# 4_GNSS.net
KiCad netlist of a schematic drawn in Altium Designer
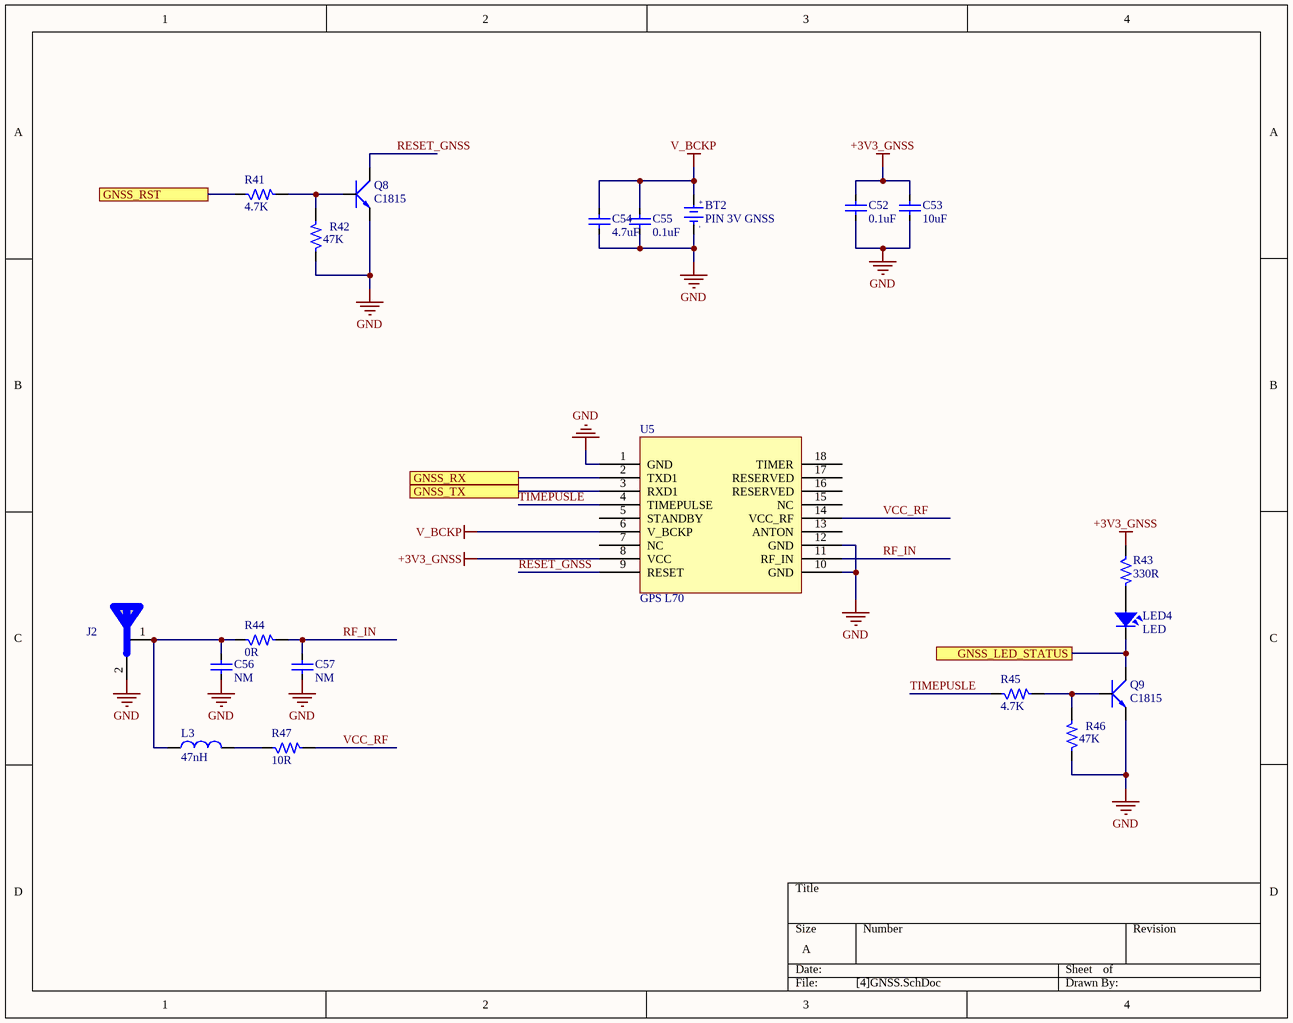
[diagram p0: [4]GNSS.SchDoc]

(export (version "E")
  (design (tool "Eeschema 10.0.6"))
  (components
    (comp (ref "BT2")
      (value "PIN 3V GNSS")
      (footprint "CR1220 SMD")
      (description "Battery 3VDC")
      (libsource (lib "GPS_Traking_V1_1") (part "PIN 3V"))
    )
    (comp (ref "C52")
      (value "0.1uF")
      (footprint "CAP_0805")
      (description "Capacitor")
      (fields (field (name "PUBLISHER") "Altium Limited"))
      (libsource (lib "My Library") (part "CapSMD"))
    )
    (comp (ref "C53")
      (value "10uF")
      (footprint "CAP_0805")
      (description "Capacitor")
      (fields (field (name "PUBLISHER") "Altium Limited"))
      (libsource (lib "My Library") (part "CapSMD"))
    )
    (comp (ref "C54")
      (value "4.7uF")
      (footprint "CAP_0805")
      (description "Capacitor")
      (fields (field (name "PUBLISHER") "Altium Limited"))
      (libsource (lib "My Library") (part "CapSMD"))
    )
    (comp (ref "C55")
      (value "0.1uF")
      (footprint "CAP_0805")
      (description "Capacitor")
      (fields (field (name "PUBLISHER") "Altium Limited"))
      (libsource (lib "My Library") (part "CapSMD"))
    )
    (comp (ref "C56")
      (value "NM")
      (footprint "CAP_0805")
      (description "Capacitor")
      (fields (field (name "PUBLISHER") "Altium Limited"))
      (libsource (lib "My Library") (part "CapSMD"))
    )
    (comp (ref "C57")
      (value "NM")
      (footprint "CAP_0805")
      (description "Capacitor")
      (fields (field (name "PUBLISHER") "Altium Limited"))
      (libsource (lib "My Library") (part "CapSMD"))
    )
    (comp (ref "J2")
      (value "GPS_ANTENNA")
      (footprint "Antenna-MCX5.08-H5")
      (libsource (lib "GPS_Traking_V1_1") (part "ANTEN"))
    )
    (comp (ref "L3")
      (value "47nH")
      (footprint "RES-SMD-0805")
      (description "Inductor")
      (libsource (lib "GPS_Traking_V1_1") (part "L1"))
    )
    (comp (ref "LED4")
      (value "LED")
      (footprint "LED-0805-Red")
      (description "LED Single colour Green and Red")
      (libsource (lib "My Library") (part "LED"))
    )
    (comp (ref "Q8")
      (value "C1815")
      (footprint "SOT23B")
      (description "NPN 600mW, ECB")
      (libsource (lib "GPS_Traking_V1_1") (part "C1815"))
    )
    (comp (ref "Q9")
      (value "C1815")
      (footprint "SOT23B")
      (description "NPN 600mW, ECB")
      (libsource (lib "GPS_Traking_V1_1") (part "C1815"))
    )
    (comp (ref "R41")
      (value "4.7K")
      (footprint "R0805")
      (description "Resistor SMD")
      (libsource (lib "GPS_Traking_V1_1") (part "RM"))
    )
    (comp (ref "R42")
      (value "47K")
      (footprint "R0805")
      (description "Resistor SMD")
      (libsource (lib "GPS_Traking_V1_1") (part "RM"))
    )
    (comp (ref "R43")
      (value "330R")
      (footprint "R0805")
      (description "Resistor SMD")
      (libsource (lib "GPS_Traking_V1_1") (part "RM"))
    )
    (comp (ref "R44")
      (value "0R")
      (footprint "R0805")
      (description "Resistor SMD")
      (libsource (lib "GPS_Traking_V1_1") (part "RM"))
    )
    (comp (ref "R45")
      (value "4.7K")
      (footprint "R0805")
      (description "Resistor SMD")
      (libsource (lib "GPS_Traking_V1_1") (part "RM"))
    )
    (comp (ref "R46")
      (value "47K")
      (footprint "R0805")
      (description "Resistor SMD")
      (libsource (lib "GPS_Traking_V1_1") (part "RM"))
    )
    (comp (ref "R47")
      (value "10R")
      (footprint "R0805")
      (description "Resistor SMD")
      (libsource (lib "GPS_Traking_V1_1") (part "RM"))
    )
    (comp (ref "U5")
      (value "GPS L70")
      (footprint "GPS L70")
      (libsource (lib "GPS_Traking_V1_1") (part "GPS L70"))
    )
  )
  (nets
    (net (code "1") (name "+3V3_GNSS") (class "Default")
      (node (ref "C52") (pin "2") (pinfunction "2_2") (pintype "passive"))
      (node (ref "C53") (pin "2") (pinfunction "2_2") (pintype "passive"))
      (node (ref "R43") (pin "1") (pinfunction "1_1") (pintype "passive"))
      (node (ref "U5") (pin "8") (pinfunction "VCC_8") (pintype "passive"))
    )
    (net (code "2") (name "/GNSS_LED_STATUS") (class "Default")
      (node (ref "LED4") (pin "2") (pinfunction "2_2") (pintype "passive"))
      (node (ref "Q9") (pin "2") (pinfunction "C_2") (pintype "passive"))
    )
    (net (code "3") (name "/GNSS_RST") (class "Default")
      (node (ref "R41") (pin "1") (pinfunction "1_1") (pintype "passive"))
    )
    (net (code "4") (name "/GNSS_RX") (class "Default")
      (node (ref "U5") (pin "2") (pinfunction "TXD1_2") (pintype "passive"))
    )
    (net (code "5") (name "/GNSS_TX") (class "Default")
      (node (ref "U5") (pin "3") (pinfunction "RXD1_3") (pintype "passive"))
    )
    (net (code "6") (name "/RESET_GNSS") (class "Default")
      (node (ref "Q8") (pin "2") (pinfunction "C_2") (pintype "passive"))
      (node (ref "U5") (pin "9") (pinfunction "RESET_9") (pintype "passive"))
    )
    (net (code "7") (name "/RF_IN") (class "Default")
      (node (ref "C57") (pin "2") (pinfunction "2_2") (pintype "passive"))
      (node (ref "R44") (pin "2") (pinfunction "2_2") (pintype "passive"))
      (node (ref "U5") (pin "11") (pinfunction "RF_IN_11") (pintype "passive"))
    )
    (net (code "8") (name "/TIMEPUSLE") (class "Default")
      (node (ref "R45") (pin "1") (pinfunction "1_1") (pintype "passive"))
      (node (ref "U5") (pin "4") (pinfunction "TIMEPULSE_4") (pintype "passive"))
    )
    (net (code "9") (name "/VCC_RF") (class "Default")
      (node (ref "R47") (pin "2") (pinfunction "2_2") (pintype "passive"))
      (node (ref "U5") (pin "14") (pinfunction "VCC_RF_14") (pintype "passive"))
    )
    (net (code "10") (name "GND") (class "Default")
      (node (ref "BT2") (pin "2") (pinfunction "GND_2") (pintype "passive"))
      (node (ref "C52") (pin "1") (pinfunction "1_1") (pintype "passive"))
      (node (ref "C53") (pin "1") (pinfunction "1_1") (pintype "passive"))
      (node (ref "C54") (pin "1") (pinfunction "1_1") (pintype "passive"))
      (node (ref "C55") (pin "1") (pinfunction "1_1") (pintype "passive"))
      (node (ref "C56") (pin "1") (pinfunction "1_1") (pintype "passive"))
      (node (ref "C57") (pin "1") (pinfunction "1_1") (pintype "passive"))
      (node (ref "J2") (pin "2") (pinfunction "GND_2") (pintype "passive"))
      (node (ref "Q8") (pin "1") (pinfunction "E_1") (pintype "passive"))
      (node (ref "Q9") (pin "1") (pinfunction "E_1") (pintype "passive"))
      (node (ref "R42") (pin "1") (pinfunction "1_1") (pintype "passive"))
      (node (ref "R46") (pin "1") (pinfunction "1_1") (pintype "passive"))
      (node (ref "U5") (pin "1") (pinfunction "GND_1") (pintype "passive"))
      (node (ref "U5") (pin "10") (pinfunction "GND_10") (pintype "passive"))
      (node (ref "U5") (pin "12") (pinfunction "GND_12") (pintype "passive"))
    )
    (net (code "11") (name "Net-(C56-Pad2)") (class "Default")
      (node (ref "C56") (pin "2") (pinfunction "2_2") (pintype "passive"))
      (node (ref "J2") (pin "1") (pinfunction "GND_1") (pintype "passive"))
      (node (ref "L3") (pin "1") (pinfunction "1_1") (pintype "passive"))
      (node (ref "R44") (pin "1") (pinfunction "1_1") (pintype "passive"))
    )
    (net (code "12") (name "Net-(L3-Pad2)") (class "Default")
      (node (ref "L3") (pin "2") (pinfunction "2_2") (pintype "passive"))
      (node (ref "R47") (pin "1") (pinfunction "1_1") (pintype "passive"))
    )
    (net (code "13") (name "Net-(LED4-Pad1)") (class "Default")
      (node (ref "LED4") (pin "1") (pinfunction "1_1") (pintype "passive"))
      (node (ref "R43") (pin "2") (pinfunction "2_2") (pintype "passive"))
    )
    (net (code "14") (name "Net-(Q8-B)") (class "Default")
      (node (ref "Q8") (pin "3") (pinfunction "B_3") (pintype "passive"))
      (node (ref "R41") (pin "2") (pinfunction "2_2") (pintype "passive"))
      (node (ref "R42") (pin "2") (pinfunction "2_2") (pintype "passive"))
    )
    (net (code "15") (name "Net-(Q9-B)") (class "Default")
      (node (ref "Q9") (pin "3") (pinfunction "B_3") (pintype "passive"))
      (node (ref "R45") (pin "2") (pinfunction "2_2") (pintype "passive"))
      (node (ref "R46") (pin "2") (pinfunction "2_2") (pintype "passive"))
    )
    (net (code "16") (name "V_BCKP") (class "Default")
      (node (ref "BT2") (pin "1") (pinfunction "+3V_1") (pintype "passive"))
      (node (ref "C54") (pin "2") (pinfunction "2_2") (pintype "passive"))
      (node (ref "C55") (pin "2") (pinfunction "2_2") (pintype "passive"))
      (node (ref "U5") (pin "6") (pinfunction "V_BCKP_6") (pintype "passive"))
    )
    (net (code "17") (name "unconnected-(U5-ANTON-Pad13)") (class "Default")
      (node (ref "U5") (pin "13") (pinfunction "ANTON_13") (pintype "passive"))
    )
    (net (code "18") (name "unconnected-(U5-NC-Pad7)") (class "Default")
      (node (ref "U5") (pin "7") (pinfunction "NC_7") (pintype "passive"))
    )
    (net (code "19") (name "unconnected-(U5-NC-Pad15)") (class "Default")
      (node (ref "U5") (pin "15") (pinfunction "NC_15") (pintype "passive"))
    )
    (net (code "20") (name "unconnected-(U5-RESERVED-Pad16)") (class "Default")
      (node (ref "U5") (pin "16") (pinfunction "RESERVED_16") (pintype "passive"))
    )
    (net (code "21") (name "unconnected-(U5-RESERVED-Pad17)") (class "Default")
      (node (ref "U5") (pin "17") (pinfunction "RESERVED_17") (pintype "passive"))
    )
    (net (code "22") (name "unconnected-(U5-STANDBY-Pad5)") (class "Default")
      (node (ref "U5") (pin "5") (pinfunction "STANDBY_5") (pintype "passive"))
    )
    (net (code "23") (name "unconnected-(U5-TIMER-Pad18)") (class "Default")
      (node (ref "U5") (pin "18") (pinfunction "TIMER_18") (pintype "passive"))
    )
  )
)
